# cubey_v2.net
KiCad netlist of a schematic drawn in EAGLE
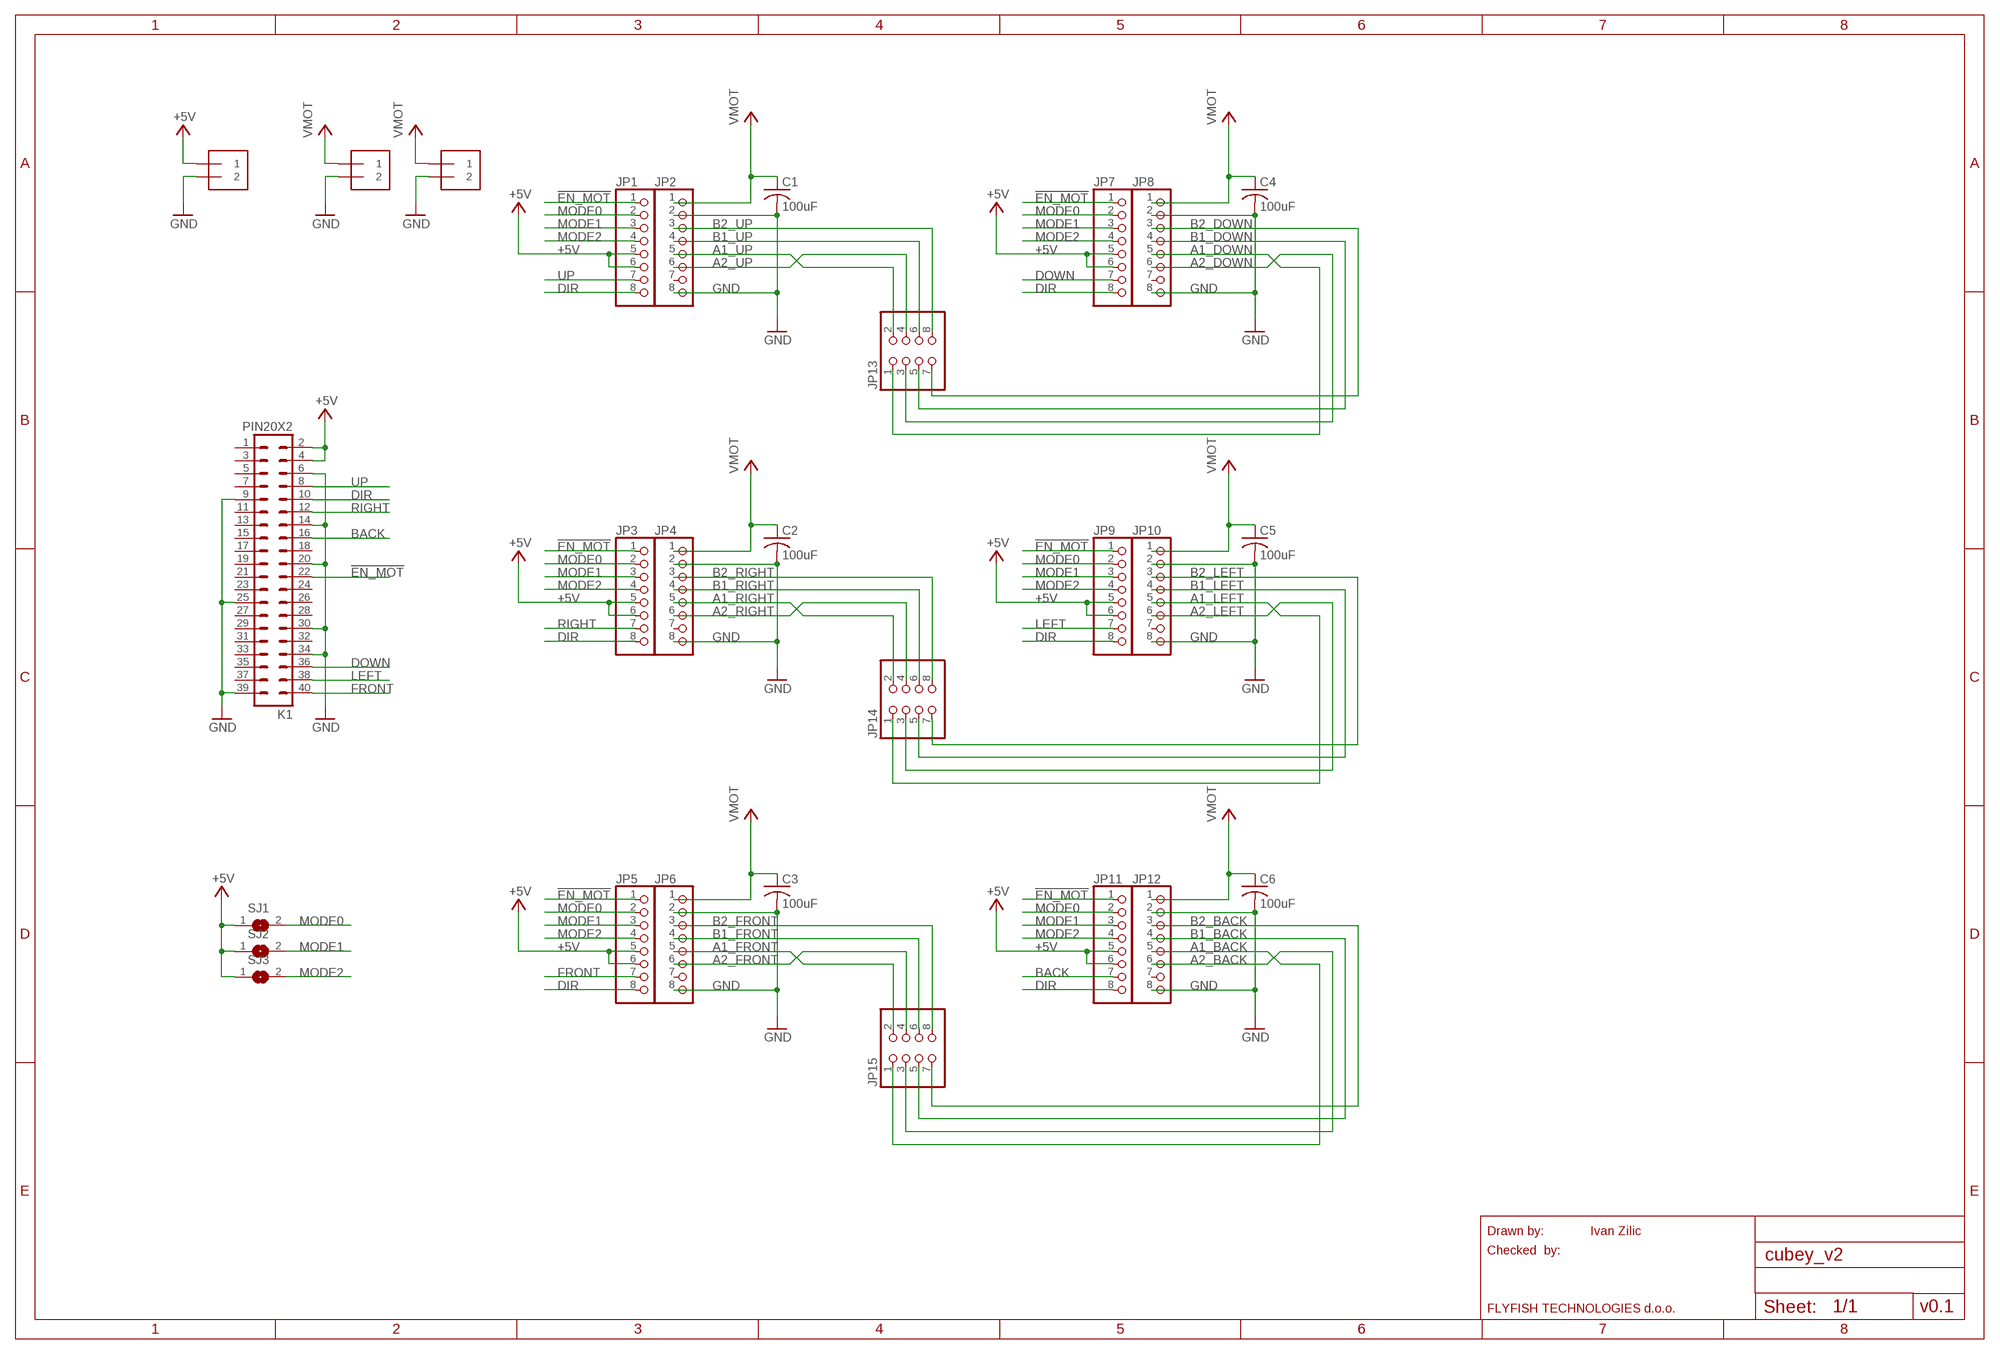
[diagram p0: schematic, sheet 1]

(export (version "E")
  (design (tool "Eeschema 10.0.6"))
  (components
    (comp (ref "5V_PWR")
      (value "1X2-3.5MM")
      (footprint "eagle-import:1X2-3.5MM")
      (libsource (lib "eagle-import") (part "1X2-3.5MM"))
    )
    (comp (ref "C1")
      (value "100uF")
      (footprint "eagle-import:C025-025X050")
      (libsource (lib "eagle-import") (part "C-US025-025X050"))
    )
    (comp (ref "C2")
      (value "100uF")
      (footprint "eagle-import:C025-025X050")
      (libsource (lib "eagle-import") (part "C-US025-025X050"))
    )
    (comp (ref "C3")
      (value "100uF")
      (footprint "eagle-import:C025-025X050")
      (libsource (lib "eagle-import") (part "C-US025-025X050"))
    )
    (comp (ref "C4")
      (value "100uF")
      (footprint "eagle-import:C025-025X050")
      (libsource (lib "eagle-import") (part "C-US025-025X050"))
    )
    (comp (ref "C5")
      (value "100uF")
      (footprint "eagle-import:C025-025X050")
      (libsource (lib "eagle-import") (part "C-US025-025X050"))
    )
    (comp (ref "C6")
      (value "100uF")
      (footprint "eagle-import:C025-025X050")
      (libsource (lib "eagle-import") (part "C-US025-025X050"))
    )
    (comp (ref "JP1")
      (value "PINHD-1X8")
      (footprint "eagle-import:1X08")
      (libsource (lib "eagle-import") (part "PINHD-1X8"))
    )
    (comp (ref "JP2")
      (value "PINHD-1X8")
      (footprint "eagle-import:1X08")
      (libsource (lib "eagle-import") (part "PINHD-1X8"))
    )
    (comp (ref "JP3")
      (value "PINHD-1X8")
      (footprint "eagle-import:1X08")
      (libsource (lib "eagle-import") (part "PINHD-1X8"))
    )
    (comp (ref "JP4")
      (value "PINHD-1X8")
      (footprint "eagle-import:1X08")
      (libsource (lib "eagle-import") (part "PINHD-1X8"))
    )
    (comp (ref "JP5")
      (value "PINHD-1X8")
      (footprint "eagle-import:1X08")
      (libsource (lib "eagle-import") (part "PINHD-1X8"))
    )
    (comp (ref "JP6")
      (value "PINHD-1X8")
      (footprint "eagle-import:1X08")
      (libsource (lib "eagle-import") (part "PINHD-1X8"))
    )
    (comp (ref "JP7")
      (value "PINHD-1X8")
      (footprint "eagle-import:1X08")
      (libsource (lib "eagle-import") (part "PINHD-1X8"))
    )
    (comp (ref "JP8")
      (value "PINHD-1X8")
      (footprint "eagle-import:1X08")
      (libsource (lib "eagle-import") (part "PINHD-1X8"))
    )
    (comp (ref "JP9")
      (value "PINHD-1X8")
      (footprint "eagle-import:1X08")
      (libsource (lib "eagle-import") (part "PINHD-1X8"))
    )
    (comp (ref "JP10")
      (value "PINHD-1X8")
      (footprint "eagle-import:1X08")
      (libsource (lib "eagle-import") (part "PINHD-1X8"))
    )
    (comp (ref "JP11")
      (value "PINHD-1X8")
      (footprint "eagle-import:1X08")
      (libsource (lib "eagle-import") (part "PINHD-1X8"))
    )
    (comp (ref "JP12")
      (value "PINHD-1X8")
      (footprint "eagle-import:1X08")
      (libsource (lib "eagle-import") (part "PINHD-1X8"))
    )
    (comp (ref "JP13")
      (value "PINHD-2X4")
      (footprint "eagle-import:2X04")
      (libsource (lib "eagle-import") (part "PINHD-2X4"))
    )
    (comp (ref "JP14")
      (value "PINHD-2X4")
      (footprint "eagle-import:2X04")
      (libsource (lib "eagle-import") (part "PINHD-2X4"))
    )
    (comp (ref "JP15")
      (value "PINHD-2X4")
      (footprint "eagle-import:2X04")
      (libsource (lib "eagle-import") (part "PINHD-2X4"))
    )
    (comp (ref "K1")
      (value "PIN20X2")
      (footprint "eagle-import:PIN_20X2")
      (libsource (lib "eagle-import") (part "PIN20X2"))
    )
    (comp (ref "MOT_PWR")
      (value "1X2-3.5MM")
      (footprint "eagle-import:1X2-3.5MM")
      (libsource (lib "eagle-import") (part "1X2-3.5MM"))
    )
    (comp (ref "MOT_PWR1")
      (value "1X2-3.5MM")
      (footprint "eagle-import:1X2-3.5MM")
      (libsource (lib "eagle-import") (part "1X2-3.5MM"))
    )
    (comp (ref "SJ1") (value "SJ") (footprint "eagle-import:SJ") (libsource (lib "eagle-import") (part "SJ")))
    (comp (ref "SJ2") (value "SJ") (footprint "eagle-import:SJ") (libsource (lib "eagle-import") (part "SJ")))
    (comp (ref "SJ3") (value "SJ") (footprint "eagle-import:SJ") (libsource (lib "eagle-import") (part "SJ")))
  )
  (nets
    (net (code "1") (name "+5V") (class "Default")
      (node (ref "5V_PWR") (pin "1") (pinfunction "1_1") (pintype "passive"))
      (node (ref "JP1") (pin "5") (pinfunction "5_5") (pintype "passive"))
      (node (ref "JP1") (pin "6") (pinfunction "6_6") (pintype "passive"))
      (node (ref "JP11") (pin "5") (pinfunction "5_5") (pintype "passive"))
      (node (ref "JP11") (pin "6") (pinfunction "6_6") (pintype "passive"))
      (node (ref "JP3") (pin "5") (pinfunction "5_5") (pintype "passive"))
      (node (ref "JP3") (pin "6") (pinfunction "6_6") (pintype "passive"))
      (node (ref "JP5") (pin "5") (pinfunction "5_5") (pintype "passive"))
      (node (ref "JP5") (pin "6") (pinfunction "6_6") (pintype "passive"))
      (node (ref "JP7") (pin "5") (pinfunction "5_5") (pintype "passive"))
      (node (ref "JP7") (pin "6") (pinfunction "6_6") (pintype "passive"))
      (node (ref "JP9") (pin "5") (pinfunction "5_5") (pintype "passive"))
      (node (ref "JP9") (pin "6") (pinfunction "6_6") (pintype "passive"))
      (node (ref "K1") (pin "2") (pinfunction "2_2") (pintype "passive"))
      (node (ref "K1") (pin "4") (pinfunction "4_4") (pintype "passive"))
      (node (ref "SJ1") (pin "1") (pinfunction "1_1") (pintype "passive"))
      (node (ref "SJ2") (pin "1") (pinfunction "1_1") (pintype "passive"))
      (node (ref "SJ3") (pin "1") (pinfunction "1_1") (pintype "passive"))
    )
    (net (code "2") (name "/A1_BACK") (class "Default")
      (node (ref "JP12") (pin "5") (pinfunction "5_5") (pintype "passive"))
      (node (ref "JP15") (pin "1") (pinfunction "1_1") (pintype "passive"))
    )
    (net (code "3") (name "/A1_DOWN") (class "Default")
      (node (ref "JP13") (pin "1") (pinfunction "1_1") (pintype "passive"))
      (node (ref "JP8") (pin "5") (pinfunction "5_5") (pintype "passive"))
    )
    (net (code "4") (name "/A1_FRONT") (class "Default")
      (node (ref "JP15") (pin "2") (pinfunction "2_2") (pintype "passive"))
      (node (ref "JP6") (pin "5") (pinfunction "5_5") (pintype "passive"))
    )
    (net (code "5") (name "/A1_LEFT") (class "Default")
      (node (ref "JP10") (pin "5") (pinfunction "5_5") (pintype "passive"))
      (node (ref "JP14") (pin "1") (pinfunction "1_1") (pintype "passive"))
    )
    (net (code "6") (name "/A1_RIGHT") (class "Default")
      (node (ref "JP14") (pin "2") (pinfunction "2_2") (pintype "passive"))
      (node (ref "JP4") (pin "5") (pinfunction "5_5") (pintype "passive"))
    )
    (net (code "7") (name "/A1_UP") (class "Default")
      (node (ref "JP13") (pin "2") (pinfunction "2_2") (pintype "passive"))
      (node (ref "JP2") (pin "5") (pinfunction "5_5") (pintype "passive"))
    )
    (net (code "8") (name "/A2_BACK") (class "Default")
      (node (ref "JP12") (pin "6") (pinfunction "6_6") (pintype "passive"))
      (node (ref "JP15") (pin "3") (pinfunction "3_3") (pintype "passive"))
    )
    (net (code "9") (name "/A2_DOWN") (class "Default")
      (node (ref "JP13") (pin "3") (pinfunction "3_3") (pintype "passive"))
      (node (ref "JP8") (pin "6") (pinfunction "6_6") (pintype "passive"))
    )
    (net (code "10") (name "/A2_FRONT") (class "Default")
      (node (ref "JP15") (pin "4") (pinfunction "4_4") (pintype "passive"))
      (node (ref "JP6") (pin "6") (pinfunction "6_6") (pintype "passive"))
    )
    (net (code "11") (name "/A2_LEFT") (class "Default")
      (node (ref "JP10") (pin "6") (pinfunction "6_6") (pintype "passive"))
      (node (ref "JP14") (pin "3") (pinfunction "3_3") (pintype "passive"))
    )
    (net (code "12") (name "/A2_RIGHT") (class "Default")
      (node (ref "JP14") (pin "4") (pinfunction "4_4") (pintype "passive"))
      (node (ref "JP4") (pin "6") (pinfunction "6_6") (pintype "passive"))
    )
    (net (code "13") (name "/A2_UP") (class "Default")
      (node (ref "JP13") (pin "4") (pinfunction "4_4") (pintype "passive"))
      (node (ref "JP2") (pin "6") (pinfunction "6_6") (pintype "passive"))
    )
    (net (code "14") (name "/B1_BACK") (class "Default")
      (node (ref "JP12") (pin "4") (pinfunction "4_4") (pintype "passive"))
      (node (ref "JP15") (pin "5") (pinfunction "5_5") (pintype "passive"))
    )
    (net (code "15") (name "/B1_DOWN") (class "Default")
      (node (ref "JP13") (pin "5") (pinfunction "5_5") (pintype "passive"))
      (node (ref "JP8") (pin "4") (pinfunction "4_4") (pintype "passive"))
    )
    (net (code "16") (name "/B1_FRONT") (class "Default")
      (node (ref "JP15") (pin "6") (pinfunction "6_6") (pintype "passive"))
      (node (ref "JP6") (pin "4") (pinfunction "4_4") (pintype "passive"))
    )
    (net (code "17") (name "/B1_LEFT") (class "Default")
      (node (ref "JP10") (pin "4") (pinfunction "4_4") (pintype "passive"))
      (node (ref "JP14") (pin "5") (pinfunction "5_5") (pintype "passive"))
    )
    (net (code "18") (name "/B1_RIGHT") (class "Default")
      (node (ref "JP14") (pin "6") (pinfunction "6_6") (pintype "passive"))
      (node (ref "JP4") (pin "4") (pinfunction "4_4") (pintype "passive"))
    )
    (net (code "19") (name "/B1_UP") (class "Default")
      (node (ref "JP13") (pin "6") (pinfunction "6_6") (pintype "passive"))
      (node (ref "JP2") (pin "4") (pinfunction "4_4") (pintype "passive"))
    )
    (net (code "20") (name "/B2_BACK") (class "Default")
      (node (ref "JP12") (pin "3") (pinfunction "3_3") (pintype "passive"))
      (node (ref "JP15") (pin "7") (pinfunction "7_7") (pintype "passive"))
    )
    (net (code "21") (name "/B2_DOWN") (class "Default")
      (node (ref "JP13") (pin "7") (pinfunction "7_7") (pintype "passive"))
      (node (ref "JP8") (pin "3") (pinfunction "3_3") (pintype "passive"))
    )
    (net (code "22") (name "/B2_FRONT") (class "Default")
      (node (ref "JP15") (pin "8") (pinfunction "8_8") (pintype "passive"))
      (node (ref "JP6") (pin "3") (pinfunction "3_3") (pintype "passive"))
    )
    (net (code "23") (name "/B2_LEFT") (class "Default")
      (node (ref "JP10") (pin "3") (pinfunction "3_3") (pintype "passive"))
      (node (ref "JP14") (pin "7") (pinfunction "7_7") (pintype "passive"))
    )
    (net (code "24") (name "/B2_RIGHT") (class "Default")
      (node (ref "JP14") (pin "8") (pinfunction "8_8") (pintype "passive"))
      (node (ref "JP4") (pin "3") (pinfunction "3_3") (pintype "passive"))
    )
    (net (code "25") (name "/B2_UP") (class "Default")
      (node (ref "JP13") (pin "8") (pinfunction "8_8") (pintype "passive"))
      (node (ref "JP2") (pin "3") (pinfunction "3_3") (pintype "passive"))
    )
    (net (code "26") (name "/BACK") (class "Default")
      (node (ref "JP11") (pin "7") (pinfunction "7_7") (pintype "passive"))
      (node (ref "K1") (pin "16") (pinfunction "16_16") (pintype "passive"))
    )
    (net (code "27") (name "/DIR") (class "Default")
      (node (ref "JP1") (pin "8") (pinfunction "8_8") (pintype "passive"))
      (node (ref "JP11") (pin "8") (pinfunction "8_8") (pintype "passive"))
      (node (ref "JP3") (pin "8") (pinfunction "8_8") (pintype "passive"))
      (node (ref "JP5") (pin "8") (pinfunction "8_8") (pintype "passive"))
      (node (ref "JP7") (pin "8") (pinfunction "8_8") (pintype "passive"))
      (node (ref "JP9") (pin "8") (pinfunction "8_8") (pintype "passive"))
      (node (ref "K1") (pin "10") (pinfunction "10_10") (pintype "passive"))
    )
    (net (code "28") (name "/DOWN") (class "Default")
      (node (ref "JP7") (pin "7") (pinfunction "7_7") (pintype "passive"))
      (node (ref "K1") (pin "36") (pinfunction "36_36") (pintype "passive"))
    )
    (net (code "29") (name "/FRONT") (class "Default")
      (node (ref "JP5") (pin "7") (pinfunction "7_7") (pintype "passive"))
      (node (ref "K1") (pin "40") (pinfunction "40_40") (pintype "passive"))
    )
    (net (code "30") (name "/LEFT") (class "Default")
      (node (ref "JP9") (pin "7") (pinfunction "7_7") (pintype "passive"))
      (node (ref "K1") (pin "38") (pinfunction "38_38") (pintype "passive"))
    )
    (net (code "31") (name "/MODE0") (class "Default")
      (node (ref "JP1") (pin "2") (pinfunction "2_2") (pintype "passive"))
      (node (ref "JP11") (pin "2") (pinfunction "2_2") (pintype "passive"))
      (node (ref "JP3") (pin "2") (pinfunction "2_2") (pintype "passive"))
      (node (ref "JP5") (pin "2") (pinfunction "2_2") (pintype "passive"))
      (node (ref "JP7") (pin "2") (pinfunction "2_2") (pintype "passive"))
      (node (ref "JP9") (pin "2") (pinfunction "2_2") (pintype "passive"))
      (node (ref "SJ1") (pin "2") (pinfunction "2_2") (pintype "passive"))
    )
    (net (code "32") (name "/MODE1") (class "Default")
      (node (ref "JP1") (pin "3") (pinfunction "3_3") (pintype "passive"))
      (node (ref "JP11") (pin "3") (pinfunction "3_3") (pintype "passive"))
      (node (ref "JP3") (pin "3") (pinfunction "3_3") (pintype "passive"))
      (node (ref "JP5") (pin "3") (pinfunction "3_3") (pintype "passive"))
      (node (ref "JP7") (pin "3") (pinfunction "3_3") (pintype "passive"))
      (node (ref "JP9") (pin "3") (pinfunction "3_3") (pintype "passive"))
      (node (ref "SJ2") (pin "2") (pinfunction "2_2") (pintype "passive"))
    )
    (net (code "33") (name "/MODE2") (class "Default")
      (node (ref "JP1") (pin "4") (pinfunction "4_4") (pintype "passive"))
      (node (ref "JP11") (pin "4") (pinfunction "4_4") (pintype "passive"))
      (node (ref "JP3") (pin "4") (pinfunction "4_4") (pintype "passive"))
      (node (ref "JP5") (pin "4") (pinfunction "4_4") (pintype "passive"))
      (node (ref "JP7") (pin "4") (pinfunction "4_4") (pintype "passive"))
      (node (ref "JP9") (pin "4") (pinfunction "4_4") (pintype "passive"))
      (node (ref "SJ3") (pin "2") (pinfunction "2_2") (pintype "passive"))
    )
    (net (code "34") (name "/RIGHT") (class "Default")
      (node (ref "JP3") (pin "7") (pinfunction "7_7") (pintype "passive"))
      (node (ref "K1") (pin "12") (pinfunction "12_12") (pintype "passive"))
    )
    (net (code "35") (name "/UP") (class "Default")
      (node (ref "JP1") (pin "7") (pinfunction "7_7") (pintype "passive"))
      (node (ref "K1") (pin "8") (pinfunction "8_8") (pintype "passive"))
    )
    (net (code "36") (name "/~{EN_MOT}") (class "Default")
      (node (ref "JP1") (pin "1") (pinfunction "1_1") (pintype "passive"))
      (node (ref "JP11") (pin "1") (pinfunction "1_1") (pintype "passive"))
      (node (ref "JP3") (pin "1") (pinfunction "1_1") (pintype "passive"))
      (node (ref "JP5") (pin "1") (pinfunction "1_1") (pintype "passive"))
      (node (ref "JP7") (pin "1") (pinfunction "1_1") (pintype "passive"))
      (node (ref "JP9") (pin "1") (pinfunction "1_1") (pintype "passive"))
      (node (ref "K1") (pin "22") (pinfunction "22_22") (pintype "passive"))
    )
    (net (code "37") (name "GND") (class "Default")
      (node (ref "5V_PWR") (pin "2") (pinfunction "2_2") (pintype "passive"))
      (node (ref "C1") (pin "2") (pinfunction "2_2") (pintype "passive"))
      (node (ref "C2") (pin "2") (pinfunction "2_2") (pintype "passive"))
      (node (ref "C3") (pin "2") (pinfunction "2_2") (pintype "passive"))
      (node (ref "C4") (pin "2") (pinfunction "2_2") (pintype "passive"))
      (node (ref "C5") (pin "2") (pinfunction "2_2") (pintype "passive"))
      (node (ref "C6") (pin "2") (pinfunction "2_2") (pintype "passive"))
      (node (ref "JP10") (pin "2") (pinfunction "2_2") (pintype "passive"))
      (node (ref "JP10") (pin "8") (pinfunction "8_8") (pintype "passive"))
      (node (ref "JP12") (pin "2") (pinfunction "2_2") (pintype "passive"))
      (node (ref "JP12") (pin "8") (pinfunction "8_8") (pintype "passive"))
      (node (ref "JP2") (pin "2") (pinfunction "2_2") (pintype "passive"))
      (node (ref "JP2") (pin "8") (pinfunction "8_8") (pintype "passive"))
      (node (ref "JP4") (pin "2") (pinfunction "2_2") (pintype "passive"))
      (node (ref "JP4") (pin "8") (pinfunction "8_8") (pintype "passive"))
      (node (ref "JP6") (pin "2") (pinfunction "2_2") (pintype "passive"))
      (node (ref "JP6") (pin "8") (pinfunction "8_8") (pintype "passive"))
      (node (ref "JP8") (pin "2") (pinfunction "2_2") (pintype "passive"))
      (node (ref "JP8") (pin "8") (pinfunction "8_8") (pintype "passive"))
      (node (ref "K1") (pin "14") (pinfunction "14_14") (pintype "passive"))
      (node (ref "K1") (pin "20") (pinfunction "20_20") (pintype "passive"))
      (node (ref "K1") (pin "25") (pinfunction "25_25") (pintype "passive"))
      (node (ref "K1") (pin "30") (pinfunction "30_30") (pintype "passive"))
      (node (ref "K1") (pin "34") (pinfunction "34_34") (pintype "passive"))
      (node (ref "K1") (pin "39") (pinfunction "39_39") (pintype "passive"))
      (node (ref "K1") (pin "6") (pinfunction "6_6") (pintype "passive"))
      (node (ref "K1") (pin "9") (pinfunction "9_9") (pintype "passive"))
      (node (ref "MOT_PWR") (pin "2") (pinfunction "2_2") (pintype "passive"))
      (node (ref "MOT_PWR1") (pin "2") (pinfunction "2_2") (pintype "passive"))
    )
    (net (code "38") (name "VMOT") (class "Default")
      (node (ref "C1") (pin "1") (pinfunction "1_1") (pintype "passive"))
      (node (ref "C2") (pin "1") (pinfunction "1_1") (pintype "passive"))
      (node (ref "C3") (pin "1") (pinfunction "1_1") (pintype "passive"))
      (node (ref "C4") (pin "1") (pinfunction "1_1") (pintype "passive"))
      (node (ref "C5") (pin "1") (pinfunction "1_1") (pintype "passive"))
      (node (ref "C6") (pin "1") (pinfunction "1_1") (pintype "passive"))
      (node (ref "JP10") (pin "1") (pinfunction "1_1") (pintype "passive"))
      (node (ref "JP12") (pin "1") (pinfunction "1_1") (pintype "passive"))
      (node (ref "JP2") (pin "1") (pinfunction "1_1") (pintype "passive"))
      (node (ref "JP4") (pin "1") (pinfunction "1_1") (pintype "passive"))
      (node (ref "JP6") (pin "1") (pinfunction "1_1") (pintype "passive"))
      (node (ref "JP8") (pin "1") (pinfunction "1_1") (pintype "passive"))
      (node (ref "MOT_PWR") (pin "1") (pinfunction "1_1") (pintype "passive"))
      (node (ref "MOT_PWR1") (pin "1") (pinfunction "1_1") (pintype "passive"))
    )
    (net (code "39") (name "unconnected-(JP2-Pad7)") (class "Default")
      (node (ref "JP2") (pin "7") (pinfunction "7_7") (pintype "passive"))
    )
    (net (code "40") (name "unconnected-(JP4-Pad7)") (class "Default")
      (node (ref "JP4") (pin "7") (pinfunction "7_7") (pintype "passive"))
    )
    (net (code "41") (name "unconnected-(JP6-Pad7)") (class "Default")
      (node (ref "JP6") (pin "7") (pinfunction "7_7") (pintype "passive"))
    )
    (net (code "42") (name "unconnected-(JP8-Pad7)") (class "Default")
      (node (ref "JP8") (pin "7") (pinfunction "7_7") (pintype "passive"))
    )
    (net (code "43") (name "unconnected-(JP10-Pad7)") (class "Default")
      (node (ref "JP10") (pin "7") (pinfunction "7_7") (pintype "passive"))
    )
    (net (code "44") (name "unconnected-(JP12-Pad7)") (class "Default")
      (node (ref "JP12") (pin "7") (pinfunction "7_7") (pintype "passive"))
    )
    (net (code "45") (name "unconnected-(K1-Pad1)") (class "Default")
      (node (ref "K1") (pin "1") (pinfunction "1_1") (pintype "passive"))
    )
    (net (code "46") (name "unconnected-(K1-Pad3)") (class "Default")
      (node (ref "K1") (pin "3") (pinfunction "3_3") (pintype "passive"))
    )
    (net (code "47") (name "unconnected-(K1-Pad5)") (class "Default")
      (node (ref "K1") (pin "5") (pinfunction "5_5") (pintype "passive"))
    )
    (net (code "48") (name "unconnected-(K1-Pad7)") (class "Default")
      (node (ref "K1") (pin "7") (pinfunction "7_7") (pintype "passive"))
    )
    (net (code "49") (name "unconnected-(K1-Pad11)") (class "Default")
      (node (ref "K1") (pin "11") (pinfunction "11_11") (pintype "passive"))
    )
    (net (code "50") (name "unconnected-(K1-Pad13)") (class "Default")
      (node (ref "K1") (pin "13") (pinfunction "13_13") (pintype "passive"))
    )
    (net (code "51") (name "unconnected-(K1-Pad15)") (class "Default")
      (node (ref "K1") (pin "15") (pinfunction "15_15") (pintype "passive"))
    )
    (net (code "52") (name "unconnected-(K1-Pad17)") (class "Default")
      (node (ref "K1") (pin "17") (pinfunction "17_17") (pintype "passive"))
    )
    (net (code "53") (name "unconnected-(K1-Pad18)") (class "Default")
      (node (ref "K1") (pin "18") (pinfunction "18_18") (pintype "passive"))
    )
    (net (code "54") (name "unconnected-(K1-Pad19)") (class "Default")
      (node (ref "K1") (pin "19") (pinfunction "19_19") (pintype "passive"))
    )
    (net (code "55") (name "unconnected-(K1-Pad21)") (class "Default")
      (node (ref "K1") (pin "21") (pinfunction "21_21") (pintype "passive"))
    )
    (net (code "56") (name "unconnected-(K1-Pad23)") (class "Default")
      (node (ref "K1") (pin "23") (pinfunction "23_23") (pintype "passive"))
    )
    (net (code "57") (name "unconnected-(K1-Pad24)") (class "Default")
      (node (ref "K1") (pin "24") (pinfunction "24_24") (pintype "passive"))
    )
    (net (code "58") (name "unconnected-(K1-Pad26)") (class "Default")
      (node (ref "K1") (pin "26") (pinfunction "26_26") (pintype "passive"))
    )
    (net (code "59") (name "unconnected-(K1-Pad27)") (class "Default")
      (node (ref "K1") (pin "27") (pinfunction "27_27") (pintype "passive"))
    )
    (net (code "60") (name "unconnected-(K1-Pad28)") (class "Default")
      (node (ref "K1") (pin "28") (pinfunction "28_28") (pintype "passive"))
    )
    (net (code "61") (name "unconnected-(K1-Pad29)") (class "Default")
      (node (ref "K1") (pin "29") (pinfunction "29_29") (pintype "passive"))
    )
    (net (code "62") (name "unconnected-(K1-Pad31)") (class "Default")
      (node (ref "K1") (pin "31") (pinfunction "31_31") (pintype "passive"))
    )
    (net (code "63") (name "unconnected-(K1-Pad32)") (class "Default")
      (node (ref "K1") (pin "32") (pinfunction "32_32") (pintype "passive"))
    )
    (net (code "64") (name "unconnected-(K1-Pad33)") (class "Default")
      (node (ref "K1") (pin "33") (pinfunction "33_33") (pintype "passive"))
    )
    (net (code "65") (name "unconnected-(K1-Pad35)") (class "Default")
      (node (ref "K1") (pin "35") (pinfunction "35_35") (pintype "passive"))
    )
    (net (code "66") (name "unconnected-(K1-Pad37)") (class "Default")
      (node (ref "K1") (pin "37") (pinfunction "37_37") (pintype "passive"))
    )
  )
)
